# Schematic.net
KiCad netlist of a schematic drawn in Altium Designer
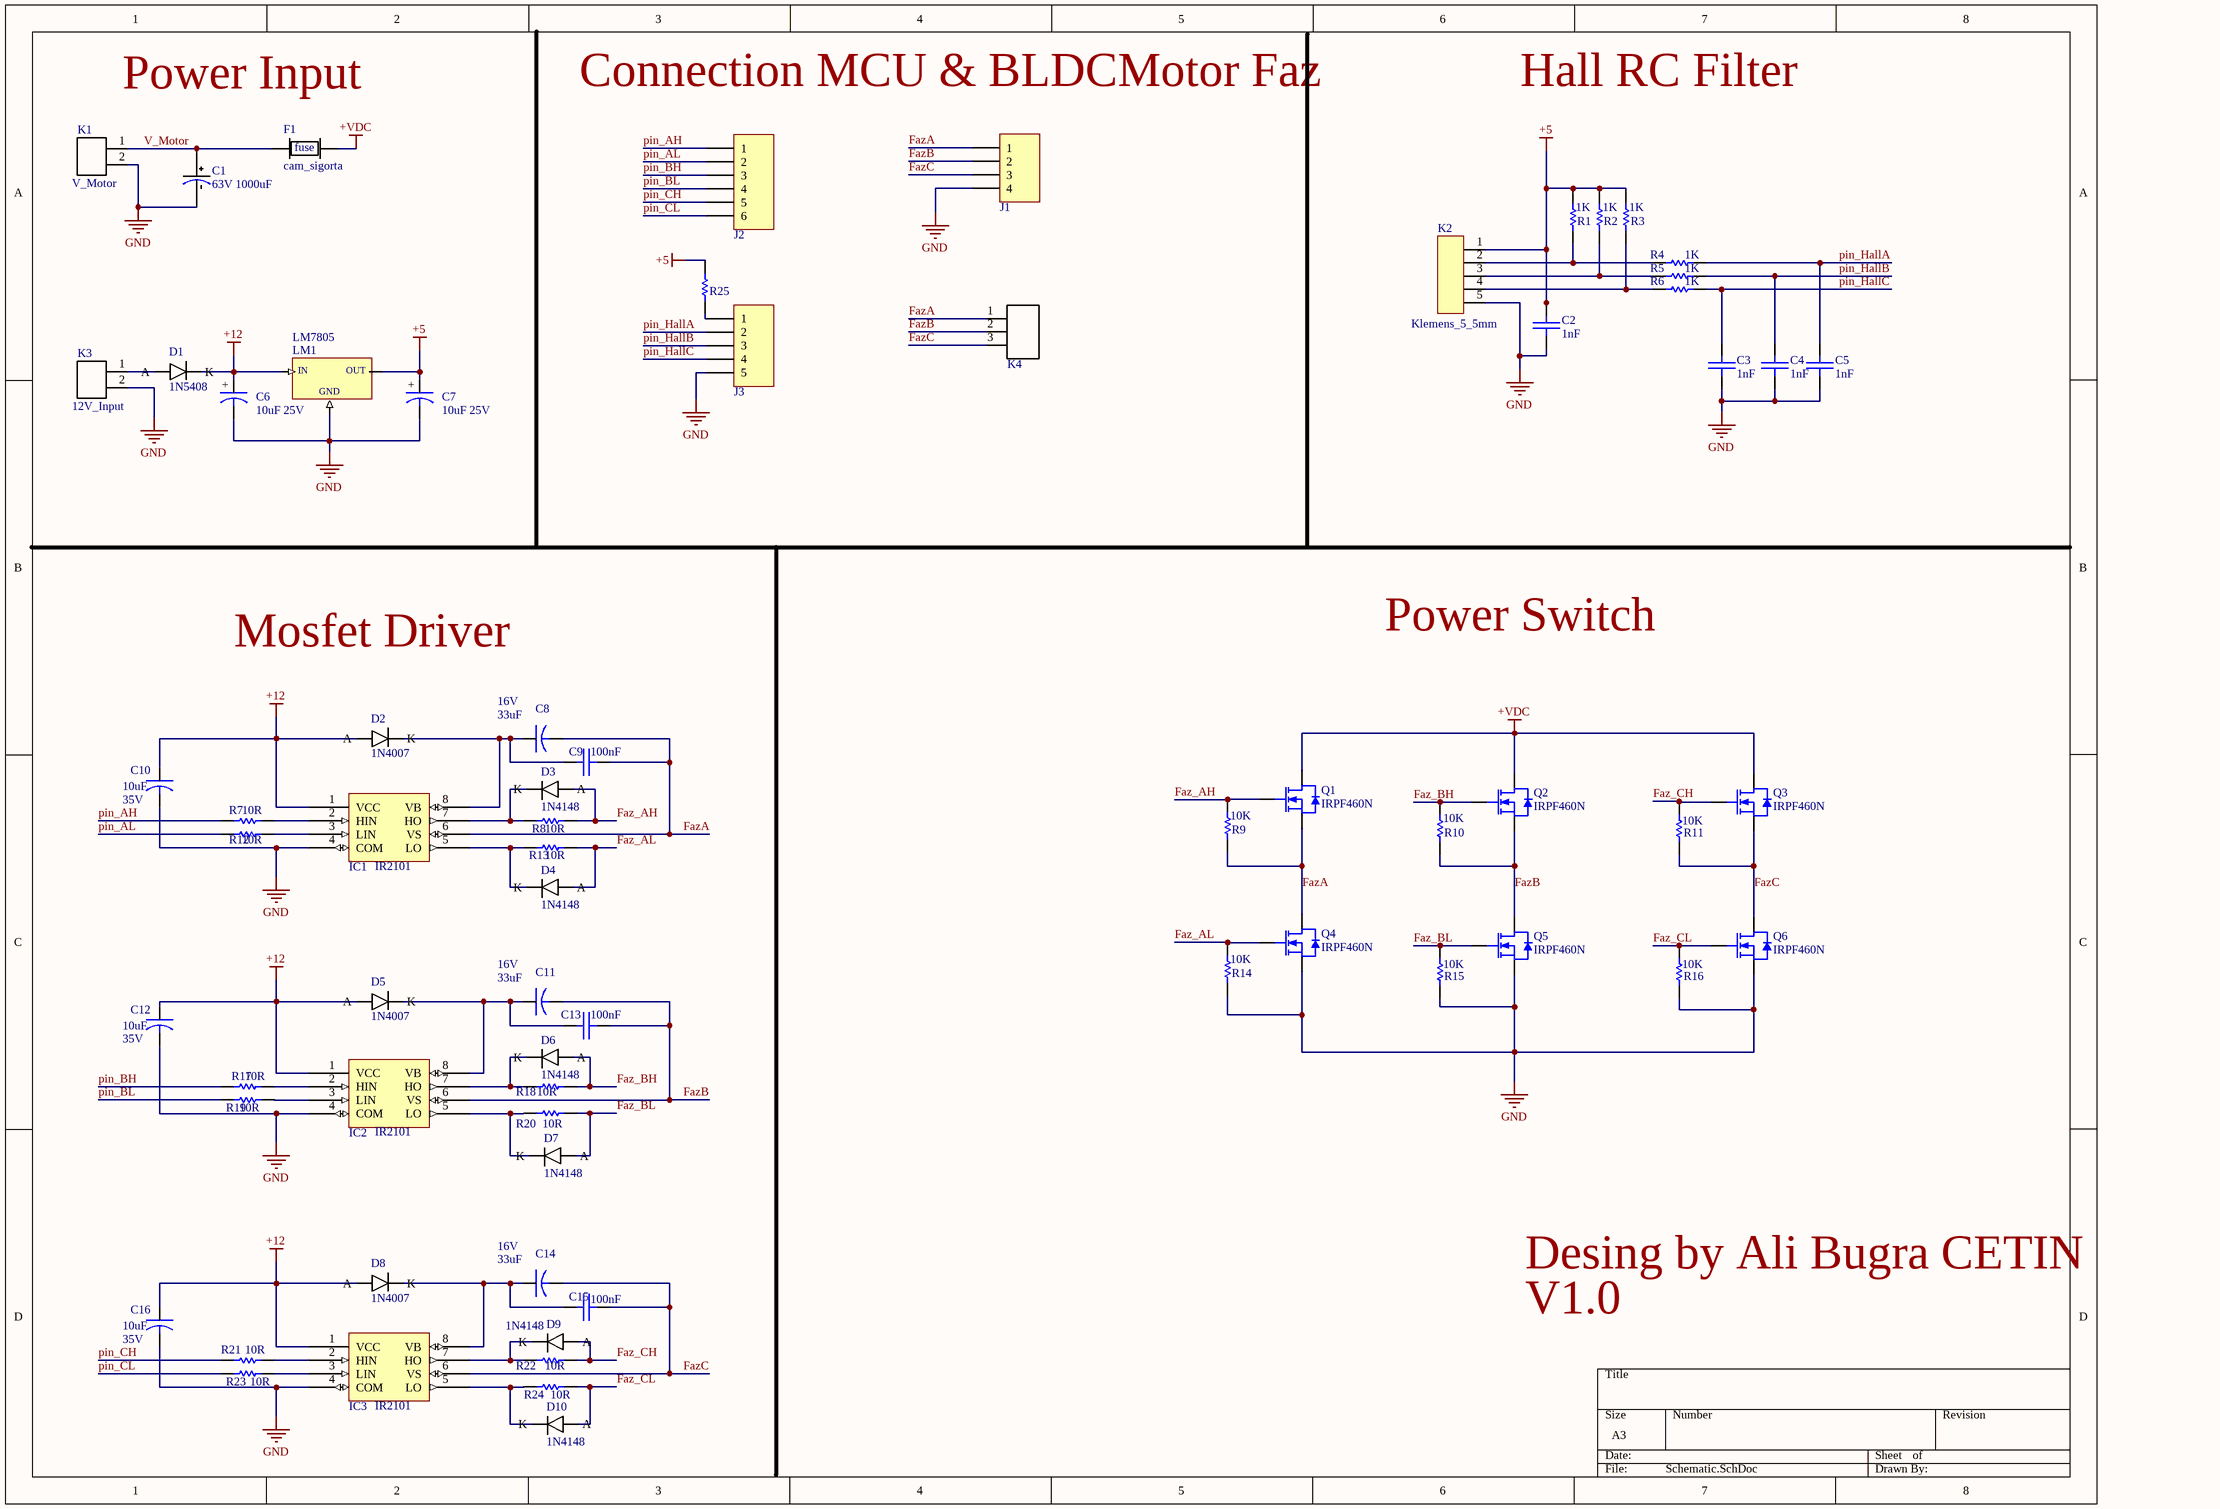
[diagram p0: Schematic.SchDoc]

(export (version "E")
  (design (tool "Eeschema 10.0.6"))
  (components
    (comp (ref "C1")
      (value "63V 1000uF")
      (footprint "1000uF 10V")
      (libsource (lib "capacitors") (part "1000uF 10V"))
    )
    (comp (ref "C2") (value "1nF") (footprint "100nF") (libsource (lib "capacitors") (part "100nF")))
    (comp (ref "C3") (value "1nF") (footprint "100nF") (libsource (lib "capacitors") (part "100nF")))
    (comp (ref "C4") (value "1nF") (footprint "100nF") (libsource (lib "capacitors") (part "100nF")))
    (comp (ref "C5") (value "1nF") (footprint "100nF") (libsource (lib "capacitors") (part "100nF")))
    (comp (ref "C6")
      (value "10uF 25V")
      (footprint "10uF 35V")
      (libsource (lib "capacitors") (part "10uF 35V"))
    )
    (comp (ref "C7")
      (value "10uF 25V")
      (footprint "10uF 35V")
      (libsource (lib "capacitors") (part "10uF 35V"))
    )
    (comp (ref "C8")
      (value "33uF")
      (footprint "100uF 25v")
      (fields
        (field (name "MANUFACTURER") "Panasonic")
        (field (name "VOLTAGE") "16V")
        (field (name "Comment") "100uF 25v")
      )
      (libsource (lib "capacitors") (part "100uF 25v"))
    )
    (comp (ref "C9") (value "100nF") (footprint "100nF") (libsource (lib "capacitors") (part "100nF")))
    (comp (ref "C10")
      (value "10uF")
      (footprint "100uF 25v")
      (fields
        (field (name "MANUFACTURER") "Panasonic")
        (field (name "VOLTAGE") "35V")
        (field (name "Comment") "100uF 25v")
      )
      (libsource (lib "capacitors") (part "100uF 25v"))
    )
    (comp (ref "C11")
      (value "33uF")
      (footprint "100uF 25v")
      (fields
        (field (name "MANUFACTURER") "Panasonic")
        (field (name "VOLTAGE") "16V")
        (field (name "Comment") "100uF 25v")
      )
      (libsource (lib "capacitors") (part "100uF 25v"))
    )
    (comp (ref "C12")
      (value "10uF")
      (footprint "100uF 25v")
      (fields
        (field (name "MANUFACTURER") "Panasonic")
        (field (name "VOLTAGE") "35V")
        (field (name "Comment") "100uF 25v")
      )
      (libsource (lib "capacitors") (part "100uF 25v"))
    )
    (comp (ref "C13") (value "100nF") (footprint "100nF") (libsource (lib "capacitors") (part "100nF")))
    (comp (ref "C14")
      (value "33uF")
      (footprint "100uF 25v")
      (fields
        (field (name "MANUFACTURER") "Panasonic")
        (field (name "VOLTAGE") "16V")
        (field (name "Comment") "100uF 25v")
      )
      (libsource (lib "capacitors") (part "100uF 25v"))
    )
    (comp (ref "C15") (value "100nF") (footprint "100nF") (libsource (lib "capacitors") (part "100nF")))
    (comp (ref "C16")
      (value "10uF")
      (footprint "100uF 25v")
      (fields
        (field (name "MANUFACTURER") "Panasonic")
        (field (name "VOLTAGE") "35V")
        (field (name "Comment") "100uF 25v")
      )
      (libsource (lib "capacitors") (part "100uF 25v"))
    )
    (comp (ref "D1") (value "1N5408") (footprint "1N5408") (libsource (lib "Diode") (part "1N5408")))
    (comp (ref "D2") (value "1N4007") (footprint "1N4007") (libsource (lib "Diode") (part "1N4007")))
    (comp (ref "D3") (value "1N4148") (footprint "1N4148") (libsource (lib "Diode") (part "1N4148")))
    (comp (ref "D4") (value "1N4148") (footprint "1N4148") (libsource (lib "Diode") (part "1N4148")))
    (comp (ref "D5") (value "1N4007") (footprint "1N4007") (libsource (lib "Diode") (part "1N4007")))
    (comp (ref "D6") (value "1N4148") (footprint "1N4148") (libsource (lib "Diode") (part "1N4148")))
    (comp (ref "D7") (value "1N4148") (footprint "1N4148") (libsource (lib "Diode") (part "1N4148")))
    (comp (ref "D8") (value "1N4007") (footprint "1N4007") (libsource (lib "Diode") (part "1N4007")))
    (comp (ref "D9") (value "1N4148") (footprint "1N4148") (libsource (lib "Diode") (part "1N4148")))
    (comp (ref "D10") (value "1N4148") (footprint "1N4148") (libsource (lib "Diode") (part "1N4148")))
    (comp (ref "F1")
      (value "cam_sigorta")
      (footprint "cam_sigorta")
      (libsource (lib "Fuse") (part "cam_sigorta"))
    )
    (comp (ref "IC1") (value "IR2101") (footprint "IR2101-DIP") (libsource (lib "Entegre") (part "IR2101")))
    (comp (ref "IC2") (value "IR2101") (footprint "IR2101-DIP") (libsource (lib "Entegre") (part "IR2101")))
    (comp (ref "IC3") (value "IR2101") (footprint "IR2101-DIP") (libsource (lib "Entegre") (part "IR2101")))
    (comp (ref "J1")
      (value "Header 4x1")
      (footprint "Header 4x1")
      (libsource (lib "Header") (part "Header 4x1"))
    )
    (comp (ref "J2")
      (value "Header 6x1")
      (footprint "Header 6x1")
      (libsource (lib "Header") (part "Header 6x1"))
    )
    (comp (ref "J3")
      (value "Header 5x1")
      (footprint "Header 5x1")
      (libsource (lib "Header") (part "Header 5x1"))
    )
    (comp (ref "K1")
      (value "V_Motor")
      (footprint "Klamens_2_3.5mm")
      (libsource (lib "Header") (part "Klamens_2_3.5mm"))
    )
    (comp (ref "K2")
      (value "Klemens_5_5mm")
      (footprint "Klamens_5_5mm")
      (libsource (lib "Header") (part "Klemens_5_5mm"))
    )
    (comp (ref "K3")
      (value "12V_Input")
      (footprint "Klamens_2_3.5mm")
      (libsource (lib "Header") (part "Klamens_2_3.5mm"))
    )
    (comp (ref "K4")
      (value "Klemens_3_7.6mm")
      (footprint "Klamens_3_7.6mm")
      (libsource (lib "Header") (part "Klemens_3_7.6mm"))
    )
    (comp (ref "LM1") (value "LM7805") (footprint "LM7805") (libsource (lib "Regulator") (part "LM7805")))
    (comp (ref "Q1")
      (value "IRPF460N")
      (footprint "IRFP460N")
      (libsource (lib "Mosfet_BJT") (part "IRPF460N"))
    )
    (comp (ref "Q2") (value "IRPF460N") (footprint "IRFP460N") (libsource (lib "") (part "IRPF460N_1")))
    (comp (ref "Q3") (value "IRPF460N") (footprint "IRFP460N") (libsource (lib "") (part "IRPF460N_1")))
    (comp (ref "Q4")
      (value "IRPF460N")
      (footprint "IRFP460N")
      (libsource (lib "Mosfet_BJT") (part "IRPF460N"))
    )
    (comp (ref "Q5") (value "IRPF460N") (footprint "IRFP460N") (libsource (lib "") (part "IRPF460N_1")))
    (comp (ref "Q6") (value "IRPF460N") (footprint "IRFP460N") (libsource (lib "") (part "IRPF460N_1")))
    (comp (ref "R1") (value "1K") (footprint "RES_DIP") (libsource (lib "RES") (part "RES_DIP")))
    (comp (ref "R2") (value "1K") (footprint "RES_DIP") (libsource (lib "RES") (part "RES_DIP")))
    (comp (ref "R3") (value "1K") (footprint "RES_DIP") (libsource (lib "RES") (part "RES_DIP")))
    (comp (ref "R4") (value "1K") (footprint "RES_DIP") (libsource (lib "RES") (part "RES_DIP")))
    (comp (ref "R5") (value "1K") (footprint "RES_DIP") (libsource (lib "RES") (part "RES_DIP")))
    (comp (ref "R6") (value "1K") (footprint "RES_DIP") (libsource (lib "RES") (part "RES_DIP")))
    (comp (ref "R7") (value "10R") (footprint "RES_DIP") (libsource (lib "RES") (part "RES_DIP")))
    (comp (ref "R8") (value "10R") (footprint "RES_DIP") (libsource (lib "RES") (part "RES_DIP")))
    (comp (ref "R9") (value "10K") (footprint "RES_DIP") (libsource (lib "RES") (part "RES_DIP")))
    (comp (ref "R10") (value "10K") (footprint "RES_DIP") (libsource (lib "RES") (part "RES_DIP")))
    (comp (ref "R11") (value "10K") (footprint "RES_DIP") (libsource (lib "RES") (part "RES_DIP")))
    (comp (ref "R12") (value "10R") (footprint "RES_DIP") (libsource (lib "RES") (part "RES_DIP")))
    (comp (ref "R13") (value "10R") (footprint "RES_DIP") (libsource (lib "RES") (part "RES_DIP")))
    (comp (ref "R14") (value "10K") (footprint "RES_DIP") (libsource (lib "RES") (part "RES_DIP")))
    (comp (ref "R15") (value "10K") (footprint "RES_DIP") (libsource (lib "RES") (part "RES_DIP")))
    (comp (ref "R16") (value "10K") (footprint "RES_DIP") (libsource (lib "RES") (part "RES_DIP")))
    (comp (ref "R17") (value "10R") (footprint "RES_DIP") (libsource (lib "RES") (part "RES_DIP")))
    (comp (ref "R18") (value "10R") (footprint "RES_DIP") (libsource (lib "RES") (part "RES_DIP")))
    (comp (ref "R19") (value "10R") (footprint "RES_DIP") (libsource (lib "RES") (part "RES_DIP")))
    (comp (ref "R20") (value "10R") (footprint "RES_DIP") (libsource (lib "RES") (part "RES_DIP")))
    (comp (ref "R21") (value "10R") (footprint "RES_DIP") (libsource (lib "RES") (part "RES_DIP")))
    (comp (ref "R22") (value "10R") (footprint "RES_DIP") (libsource (lib "RES") (part "RES_DIP")))
    (comp (ref "R23") (value "10R") (footprint "RES_DIP") (libsource (lib "RES") (part "RES_DIP")))
    (comp (ref "R24") (value "10R") (footprint "RES_DIP") (libsource (lib "RES") (part "RES_DIP")))
    (comp (ref "R25") (value "RES_DIP") (footprint "RES_DIP") (libsource (lib "RES") (part "RES_DIP")))
  )
  (nets
    (net (code "1") (name "+5") (class "Default")
      (node (ref "C2") (pin "1") (pinfunction "1_1") (pintype "passive"))
      (node (ref "C7") (pin "+") (pinfunction "+_+") (pintype "passive"))
      (node (ref "K2") (pin "1") (pinfunction "1_1") (pintype "passive"))
      (node (ref "LM1") (pin "OUT") (pinfunction "OUT_OUT") (pintype "passive"))
      (node (ref "R1") (pin "2") (pinfunction "2_2") (pintype "passive"))
      (node (ref "R2") (pin "2") (pinfunction "2_2") (pintype "passive"))
      (node (ref "R25") (pin "1") (pinfunction "1_1") (pintype "passive"))
      (node (ref "R3") (pin "2") (pinfunction "2_2") (pintype "passive"))
    )
    (net (code "2") (name "+12") (class "Default")
      (node (ref "C10") (pin "1") (pinfunction "1_1") (pintype "passive"))
      (node (ref "C12") (pin "1") (pinfunction "1_1") (pintype "passive"))
      (node (ref "C16") (pin "1") (pinfunction "1_1") (pintype "passive"))
      (node (ref "C6") (pin "+") (pinfunction "+_+") (pintype "passive"))
      (node (ref "D1") (pin "2") (pinfunction "K_2") (pintype "passive"))
      (node (ref "D2") (pin "1") (pinfunction "A_1") (pintype "passive"))
      (node (ref "D5") (pin "1") (pinfunction "A_1") (pintype "passive"))
      (node (ref "D8") (pin "1") (pinfunction "A_1") (pintype "passive"))
      (node (ref "IC1") (pin "1") (pinfunction "VCC_1") (pintype "power_in"))
      (node (ref "IC2") (pin "1") (pinfunction "VCC_1") (pintype "power_in"))
      (node (ref "IC3") (pin "1") (pinfunction "VCC_1") (pintype "power_in"))
      (node (ref "LM1") (pin "IN") (pinfunction "IN_IN") (pintype "input"))
    )
    (net (code "3") (name "+VDC") (class "Default")
      (node (ref "F1") (pin "2") (pinfunction "2_2") (pintype "passive"))
      (node (ref "Q1") (pin "2") (pinfunction "D_2") (pintype "passive"))
      (node (ref "Q2") (pin "2") (pinfunction "D_2") (pintype "passive"))
      (node (ref "Q3") (pin "2") (pinfunction "D_2") (pintype "passive"))
    )
    (net (code "4") (name "/FazA") (class "Default")
      (node (ref "C8") (pin "2") (pinfunction "2_2") (pintype "passive"))
      (node (ref "C9") (pin "2") (pinfunction "2_2") (pintype "passive"))
      (node (ref "IC1") (pin "6") (pinfunction "VS_6") (pintype "bidirectional"))
      (node (ref "J1") (pin "1") (pinfunction "1_1") (pintype "passive"))
      (node (ref "K4") (pin "1") (pinfunction "1_1") (pintype "passive"))
      (node (ref "Q1") (pin "3") (pinfunction "S_3") (pintype "passive"))
      (node (ref "Q4") (pin "2") (pinfunction "D_2") (pintype "passive"))
      (node (ref "R9") (pin "1") (pinfunction "1_1") (pintype "passive"))
    )
    (net (code "5") (name "/FazB") (class "Default")
      (node (ref "C11") (pin "2") (pinfunction "2_2") (pintype "passive"))
      (node (ref "C13") (pin "2") (pinfunction "2_2") (pintype "passive"))
      (node (ref "IC2") (pin "6") (pinfunction "VS_6") (pintype "bidirectional"))
      (node (ref "J1") (pin "2") (pinfunction "2_2") (pintype "passive"))
      (node (ref "K4") (pin "2") (pinfunction "2_2") (pintype "passive"))
      (node (ref "Q2") (pin "3") (pinfunction "S_3") (pintype "passive"))
      (node (ref "Q5") (pin "2") (pinfunction "D_2") (pintype "passive"))
      (node (ref "R10") (pin "1") (pinfunction "1_1") (pintype "passive"))
    )
    (net (code "6") (name "/FazC") (class "Default")
      (node (ref "C14") (pin "2") (pinfunction "2_2") (pintype "passive"))
      (node (ref "C15") (pin "2") (pinfunction "2_2") (pintype "passive"))
      (node (ref "IC3") (pin "6") (pinfunction "VS_6") (pintype "bidirectional"))
      (node (ref "J1") (pin "3") (pinfunction "3_3") (pintype "passive"))
      (node (ref "K4") (pin "3") (pinfunction "3_3") (pintype "passive"))
      (node (ref "Q3") (pin "3") (pinfunction "S_3") (pintype "passive"))
      (node (ref "Q6") (pin "2") (pinfunction "D_2") (pintype "passive"))
      (node (ref "R11") (pin "1") (pinfunction "1_1") (pintype "passive"))
    )
    (net (code "7") (name "/Faz_AH") (class "Default")
      (node (ref "D3") (pin "1") (pinfunction "A_1") (pintype "passive"))
      (node (ref "Q1") (pin "1") (pinfunction "G_1") (pintype "passive"))
      (node (ref "R8") (pin "2") (pinfunction "2_2") (pintype "passive"))
      (node (ref "R9") (pin "2") (pinfunction "2_2") (pintype "passive"))
    )
    (net (code "8") (name "/Faz_AL") (class "Default")
      (node (ref "D4") (pin "1") (pinfunction "A_1") (pintype "passive"))
      (node (ref "Q4") (pin "1") (pinfunction "G_1") (pintype "passive"))
      (node (ref "R13") (pin "2") (pinfunction "2_2") (pintype "passive"))
      (node (ref "R14") (pin "2") (pinfunction "2_2") (pintype "passive"))
    )
    (net (code "9") (name "/Faz_BH") (class "Default")
      (node (ref "D6") (pin "1") (pinfunction "A_1") (pintype "passive"))
      (node (ref "Q2") (pin "1") (pinfunction "G_1") (pintype "passive"))
      (node (ref "R10") (pin "2") (pinfunction "2_2") (pintype "passive"))
      (node (ref "R18") (pin "2") (pinfunction "2_2") (pintype "passive"))
    )
    (net (code "10") (name "/Faz_BL") (class "Default")
      (node (ref "D7") (pin "1") (pinfunction "A_1") (pintype "passive"))
      (node (ref "Q5") (pin "1") (pinfunction "G_1") (pintype "passive"))
      (node (ref "R15") (pin "2") (pinfunction "2_2") (pintype "passive"))
      (node (ref "R20") (pin "2") (pinfunction "2_2") (pintype "passive"))
    )
    (net (code "11") (name "/Faz_CH") (class "Default")
      (node (ref "D9") (pin "1") (pinfunction "A_1") (pintype "passive"))
      (node (ref "Q3") (pin "1") (pinfunction "G_1") (pintype "passive"))
      (node (ref "R11") (pin "2") (pinfunction "2_2") (pintype "passive"))
      (node (ref "R22") (pin "2") (pinfunction "2_2") (pintype "passive"))
    )
    (net (code "12") (name "/Faz_CL") (class "Default")
      (node (ref "D10") (pin "1") (pinfunction "A_1") (pintype "passive"))
      (node (ref "Q6") (pin "1") (pinfunction "G_1") (pintype "passive"))
      (node (ref "R16") (pin "2") (pinfunction "2_2") (pintype "passive"))
      (node (ref "R24") (pin "2") (pinfunction "2_2") (pintype "passive"))
    )
    (net (code "13") (name "/V_Motor") (class "Default")
      (node (ref "C1") (pin "POS") (pinfunction "POS_POS") (pintype "passive"))
      (node (ref "F1") (pin "1") (pinfunction "1_1") (pintype "passive"))
      (node (ref "K1") (pin "1") (pinfunction "1_1") (pintype "passive"))
    )
    (net (code "14") (name "/pin_AH") (class "Default")
      (node (ref "J2") (pin "1") (pinfunction "1_1") (pintype "passive"))
      (node (ref "R7") (pin "1") (pinfunction "1_1") (pintype "passive"))
    )
    (net (code "15") (name "/pin_AL") (class "Default")
      (node (ref "J2") (pin "2") (pinfunction "2_2") (pintype "passive"))
      (node (ref "R12") (pin "1") (pinfunction "1_1") (pintype "passive"))
    )
    (net (code "16") (name "/pin_BH") (class "Default")
      (node (ref "J2") (pin "3") (pinfunction "3_3") (pintype "passive"))
      (node (ref "R17") (pin "1") (pinfunction "1_1") (pintype "passive"))
    )
    (net (code "17") (name "/pin_BL") (class "Default")
      (node (ref "J2") (pin "4") (pinfunction "4_4") (pintype "passive"))
      (node (ref "R19") (pin "1") (pinfunction "1_1") (pintype "passive"))
    )
    (net (code "18") (name "/pin_CH") (class "Default")
      (node (ref "J2") (pin "5") (pinfunction "5_5") (pintype "passive"))
      (node (ref "R21") (pin "1") (pinfunction "1_1") (pintype "passive"))
    )
    (net (code "19") (name "/pin_CL") (class "Default")
      (node (ref "J2") (pin "6") (pinfunction "6_6") (pintype "passive"))
      (node (ref "R23") (pin "1") (pinfunction "1_1") (pintype "passive"))
    )
    (net (code "20") (name "/pin_HallA") (class "Default")
      (node (ref "C5") (pin "1") (pinfunction "1_1") (pintype "passive"))
      (node (ref "J3") (pin "2") (pinfunction "2_2") (pintype "passive"))
      (node (ref "R4") (pin "2") (pinfunction "2_2") (pintype "passive"))
    )
    (net (code "21") (name "/pin_HallB") (class "Default")
      (node (ref "C4") (pin "1") (pinfunction "1_1") (pintype "passive"))
      (node (ref "J3") (pin "3") (pinfunction "3_3") (pintype "passive"))
      (node (ref "R5") (pin "2") (pinfunction "2_2") (pintype "passive"))
    )
    (net (code "22") (name "/pin_HallC") (class "Default")
      (node (ref "C3") (pin "1") (pinfunction "1_1") (pintype "passive"))
      (node (ref "J3") (pin "4") (pinfunction "4_4") (pintype "passive"))
      (node (ref "R6") (pin "2") (pinfunction "2_2") (pintype "passive"))
    )
    (net (code "23") (name "GND") (class "Default")
      (node (ref "C1") (pin "NEG") (pinfunction "NEG_NEG") (pintype "passive"))
      (node (ref "C10") (pin "2") (pinfunction "2_2") (pintype "passive"))
      (node (ref "C12") (pin "2") (pinfunction "2_2") (pintype "passive"))
      (node (ref "C16") (pin "2") (pinfunction "2_2") (pintype "passive"))
      (node (ref "C2") (pin "2") (pinfunction "2_2") (pintype "passive"))
      (node (ref "C3") (pin "2") (pinfunction "2_2") (pintype "passive"))
      (node (ref "C4") (pin "2") (pinfunction "2_2") (pintype "passive"))
      (node (ref "C5") (pin "2") (pinfunction "2_2") (pintype "passive"))
      (node (ref "C6") (pin "-") (pinfunction "-_-") (pintype "passive"))
      (node (ref "C7") (pin "-") (pinfunction "-_-") (pintype "passive"))
      (node (ref "IC1") (pin "4") (pinfunction "COM_4") (pintype "bidirectional"))
      (node (ref "IC2") (pin "4") (pinfunction "COM_4") (pintype "bidirectional"))
      (node (ref "IC3") (pin "4") (pinfunction "COM_4") (pintype "bidirectional"))
      (node (ref "J1") (pin "4") (pinfunction "4_4") (pintype "passive"))
      (node (ref "J3") (pin "5") (pinfunction "5_5") (pintype "passive"))
      (node (ref "K1") (pin "2") (pinfunction "2_2") (pintype "passive"))
      (node (ref "K2") (pin "5") (pinfunction "5_5") (pintype "passive"))
      (node (ref "K3") (pin "2") (pinfunction "2_2") (pintype "passive"))
      (node (ref "LM1") (pin "GND") (pinfunction "GND_GND") (pintype "input"))
      (node (ref "Q4") (pin "3") (pinfunction "S_3") (pintype "passive"))
      (node (ref "Q5") (pin "3") (pinfunction "S_3") (pintype "passive"))
      (node (ref "Q6") (pin "3") (pinfunction "S_3") (pintype "passive"))
      (node (ref "R14") (pin "1") (pinfunction "1_1") (pintype "passive"))
      (node (ref "R15") (pin "1") (pinfunction "1_1") (pintype "passive"))
      (node (ref "R16") (pin "1") (pinfunction "1_1") (pintype "passive"))
    )
    (net (code "24") (name "Net-(D1-A)") (class "Default")
      (node (ref "D1") (pin "1") (pinfunction "A_1") (pintype "passive"))
      (node (ref "K3") (pin "1") (pinfunction "1_1") (pintype "passive"))
    )
    (net (code "25") (name "Net-(D2-K)") (class "Default")
      (node (ref "C8") (pin "1") (pinfunction "1_1") (pintype "passive"))
      (node (ref "C9") (pin "1") (pinfunction "1_1") (pintype "passive"))
      (node (ref "D2") (pin "2") (pinfunction "K_2") (pintype "passive"))
      (node (ref "IC1") (pin "8") (pinfunction "VB_8") (pintype "bidirectional"))
    )
    (net (code "26") (name "Net-(D3-K)") (class "Default")
      (node (ref "D3") (pin "2") (pinfunction "K_2") (pintype "passive"))
      (node (ref "IC1") (pin "7") (pinfunction "HO_7") (pintype "output"))
      (node (ref "R8") (pin "1") (pinfunction "1_1") (pintype "passive"))
    )
    (net (code "27") (name "Net-(D4-K)") (class "Default")
      (node (ref "D4") (pin "2") (pinfunction "K_2") (pintype "passive"))
      (node (ref "IC1") (pin "5") (pinfunction "LO_5") (pintype "output"))
      (node (ref "R13") (pin "1") (pinfunction "1_1") (pintype "passive"))
    )
    (net (code "28") (name "Net-(D5-K)") (class "Default")
      (node (ref "C11") (pin "1") (pinfunction "1_1") (pintype "passive"))
      (node (ref "C13") (pin "1") (pinfunction "1_1") (pintype "passive"))
      (node (ref "D5") (pin "2") (pinfunction "K_2") (pintype "passive"))
      (node (ref "IC2") (pin "8") (pinfunction "VB_8") (pintype "bidirectional"))
    )
    (net (code "29") (name "Net-(D6-K)") (class "Default")
      (node (ref "D6") (pin "2") (pinfunction "K_2") (pintype "passive"))
      (node (ref "IC2") (pin "7") (pinfunction "HO_7") (pintype "output"))
      (node (ref "R18") (pin "1") (pinfunction "1_1") (pintype "passive"))
    )
    (net (code "30") (name "Net-(D7-K)") (class "Default")
      (node (ref "D7") (pin "2") (pinfunction "K_2") (pintype "passive"))
      (node (ref "IC2") (pin "5") (pinfunction "LO_5") (pintype "output"))
      (node (ref "R20") (pin "1") (pinfunction "1_1") (pintype "passive"))
    )
    (net (code "31") (name "Net-(D8-K)") (class "Default")
      (node (ref "C14") (pin "1") (pinfunction "1_1") (pintype "passive"))
      (node (ref "C15") (pin "1") (pinfunction "1_1") (pintype "passive"))
      (node (ref "D8") (pin "2") (pinfunction "K_2") (pintype "passive"))
      (node (ref "IC3") (pin "8") (pinfunction "VB_8") (pintype "bidirectional"))
    )
    (net (code "32") (name "Net-(D9-K)") (class "Default")
      (node (ref "D9") (pin "2") (pinfunction "K_2") (pintype "passive"))
      (node (ref "IC3") (pin "7") (pinfunction "HO_7") (pintype "output"))
      (node (ref "R22") (pin "1") (pinfunction "1_1") (pintype "passive"))
    )
    (net (code "33") (name "Net-(D10-K)") (class "Default")
      (node (ref "D10") (pin "2") (pinfunction "K_2") (pintype "passive"))
      (node (ref "IC3") (pin "5") (pinfunction "LO_5") (pintype "output"))
      (node (ref "R24") (pin "1") (pinfunction "1_1") (pintype "passive"))
    )
    (net (code "34") (name "Net-(IC1-HIN)") (class "Default")
      (node (ref "IC1") (pin "2") (pinfunction "HIN_2") (pintype "input"))
      (node (ref "R7") (pin "2") (pinfunction "2_2") (pintype "passive"))
    )
    (net (code "35") (name "Net-(IC1-LIN)") (class "Default")
      (node (ref "IC1") (pin "3") (pinfunction "LIN_3") (pintype "input"))
      (node (ref "R12") (pin "2") (pinfunction "2_2") (pintype "passive"))
    )
    (net (code "36") (name "Net-(IC2-HIN)") (class "Default")
      (node (ref "IC2") (pin "2") (pinfunction "HIN_2") (pintype "input"))
      (node (ref "R17") (pin "2") (pinfunction "2_2") (pintype "passive"))
    )
    (net (code "37") (name "Net-(IC2-LIN)") (class "Default")
      (node (ref "IC2") (pin "3") (pinfunction "LIN_3") (pintype "input"))
      (node (ref "R19") (pin "2") (pinfunction "2_2") (pintype "passive"))
    )
    (net (code "38") (name "Net-(IC3-HIN)") (class "Default")
      (node (ref "IC3") (pin "2") (pinfunction "HIN_2") (pintype "input"))
      (node (ref "R21") (pin "2") (pinfunction "2_2") (pintype "passive"))
    )
    (net (code "39") (name "Net-(IC3-LIN)") (class "Default")
      (node (ref "IC3") (pin "3") (pinfunction "LIN_3") (pintype "input"))
      (node (ref "R23") (pin "2") (pinfunction "2_2") (pintype "passive"))
    )
    (net (code "40") (name "Net-(J3-Pad1)") (class "Default")
      (node (ref "J3") (pin "1") (pinfunction "1_1") (pintype "passive"))
      (node (ref "R25") (pin "2") (pinfunction "2_2") (pintype "passive"))
    )
    (net (code "41") (name "Net-(K2-Pad2)") (class "Default")
      (node (ref "K2") (pin "2") (pinfunction "2_2") (pintype "passive"))
      (node (ref "R1") (pin "1") (pinfunction "1_1") (pintype "passive"))
      (node (ref "R4") (pin "1") (pinfunction "1_1") (pintype "passive"))
    )
    (net (code "42") (name "Net-(K2-Pad3)") (class "Default")
      (node (ref "K2") (pin "3") (pinfunction "3_3") (pintype "passive"))
      (node (ref "R2") (pin "1") (pinfunction "1_1") (pintype "passive"))
      (node (ref "R5") (pin "1") (pinfunction "1_1") (pintype "passive"))
    )
    (net (code "43") (name "Net-(K2-Pad4)") (class "Default")
      (node (ref "K2") (pin "4") (pinfunction "4_4") (pintype "passive"))
      (node (ref "R3") (pin "1") (pinfunction "1_1") (pintype "passive"))
      (node (ref "R6") (pin "1") (pinfunction "1_1") (pintype "passive"))
    )
  )
)
